# 03_LED.net
KiCad netlist of a schematic drawn in Altium Designer
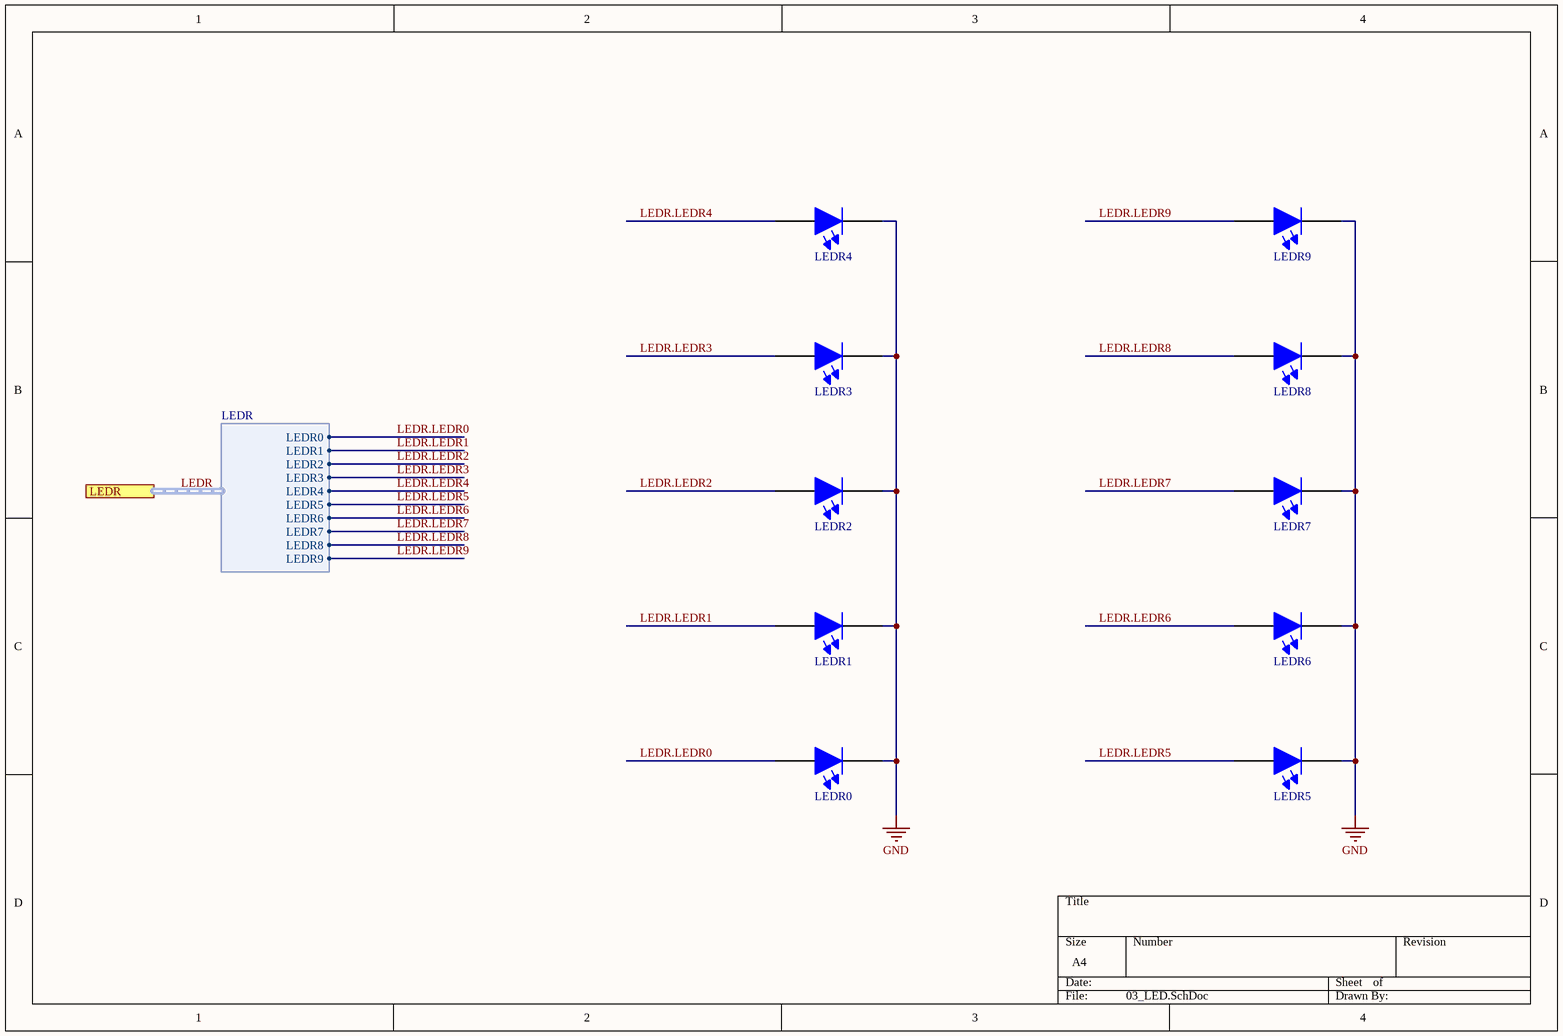
[diagram p0: 03_LED.SchDoc]

(export (version "E")
  (design (tool "Eeschema 10.0.6"))
  (components
    (comp (ref "LEDR0")
      (value "LED")
      (footprint "0805D-RED")
      (description "Generic LED")
      (fields
        (field (name "01 CREATED BY") "Thomas Harper")
        (field (name "02 REVIEWED BY") "Rodrigo Maureira @ 2018-04-05")
        (field (name "PUBLISHER") "MUEEC")
      )
      (libsource (lib "Quatro_SchLib") (part "LED_SMD_Generic"))
    )
    (comp (ref "LEDR1")
      (value "LED")
      (footprint "0805D-RED")
      (description "Generic LED")
      (fields
        (field (name "01 CREATED BY") "Thomas Harper")
        (field (name "02 REVIEWED BY") "Rodrigo Maureira @ 2018-04-05")
        (field (name "PUBLISHER") "MUEEC")
      )
      (libsource (lib "Quatro_SchLib") (part "LED_SMD_Generic"))
    )
    (comp (ref "LEDR2")
      (value "LED")
      (footprint "0805D-RED")
      (description "Generic LED")
      (fields
        (field (name "01 CREATED BY") "Thomas Harper")
        (field (name "02 REVIEWED BY") "Rodrigo Maureira @ 2018-04-05")
        (field (name "PUBLISHER") "MUEEC")
      )
      (libsource (lib "Quatro_SchLib") (part "LED_SMD_Generic"))
    )
    (comp (ref "LEDR3")
      (value "LED")
      (footprint "0805D-RED")
      (description "Generic LED")
      (fields
        (field (name "01 CREATED BY") "Thomas Harper")
        (field (name "02 REVIEWED BY") "Rodrigo Maureira @ 2018-04-05")
        (field (name "PUBLISHER") "MUEEC")
      )
      (libsource (lib "Quatro_SchLib") (part "LED_SMD_Generic"))
    )
    (comp (ref "LEDR4")
      (value "LED")
      (footprint "0805D-RED")
      (description "Generic LED")
      (fields
        (field (name "01 CREATED BY") "Thomas Harper")
        (field (name "02 REVIEWED BY") "Rodrigo Maureira @ 2018-04-05")
        (field (name "PUBLISHER") "MUEEC")
      )
      (libsource (lib "Quatro_SchLib") (part "LED_SMD_Generic"))
    )
    (comp (ref "LEDR5")
      (value "LED")
      (footprint "0805D-RED")
      (description "Generic LED")
      (fields
        (field (name "01 CREATED BY") "Thomas Harper")
        (field (name "02 REVIEWED BY") "Rodrigo Maureira @ 2018-04-05")
        (field (name "PUBLISHER") "MUEEC")
      )
      (libsource (lib "Quatro_SchLib") (part "LED_SMD_Generic"))
    )
    (comp (ref "LEDR6")
      (value "LED")
      (footprint "0805D-RED")
      (description "Generic LED")
      (fields
        (field (name "01 CREATED BY") "Thomas Harper")
        (field (name "02 REVIEWED BY") "Rodrigo Maureira @ 2018-04-05")
        (field (name "PUBLISHER") "MUEEC")
      )
      (libsource (lib "Quatro_SchLib") (part "LED_SMD_Generic"))
    )
    (comp (ref "LEDR7")
      (value "LED")
      (footprint "0805D-RED")
      (description "Generic LED")
      (fields
        (field (name "01 CREATED BY") "Thomas Harper")
        (field (name "02 REVIEWED BY") "Rodrigo Maureira @ 2018-04-05")
        (field (name "PUBLISHER") "MUEEC")
      )
      (libsource (lib "Quatro_SchLib") (part "LED_SMD_Generic"))
    )
    (comp (ref "LEDR8")
      (value "LED")
      (footprint "0805D-RED")
      (description "Generic LED")
      (fields
        (field (name "01 CREATED BY") "Thomas Harper")
        (field (name "02 REVIEWED BY") "Rodrigo Maureira @ 2018-04-05")
        (field (name "PUBLISHER") "MUEEC")
      )
      (libsource (lib "Quatro_SchLib") (part "LED_SMD_Generic"))
    )
    (comp (ref "LEDR9")
      (value "LED")
      (footprint "0805D-RED")
      (description "Generic LED")
      (fields
        (field (name "01 CREATED BY") "Thomas Harper")
        (field (name "02 REVIEWED BY") "Rodrigo Maureira @ 2018-04-05")
        (field (name "PUBLISHER") "MUEEC")
      )
      (libsource (lib "Quatro_SchLib") (part "LED_SMD_Generic"))
    )
  )
  (nets
    (net (code "2") (name "/LEDR.LEDR0") (class "Default")
      (node (ref "LEDR0") (pin "A") (pinfunction "ANODE_A") (pintype "passive"))
    )
    (net (code "3") (name "/LEDR.LEDR1") (class "Default")
      (node (ref "LEDR1") (pin "A") (pinfunction "ANODE_A") (pintype "passive"))
    )
    (net (code "4") (name "/LEDR.LEDR2") (class "Default")
      (node (ref "LEDR2") (pin "A") (pinfunction "ANODE_A") (pintype "passive"))
    )
    (net (code "5") (name "/LEDR.LEDR3") (class "Default")
      (node (ref "LEDR3") (pin "A") (pinfunction "ANODE_A") (pintype "passive"))
    )
    (net (code "6") (name "/LEDR.LEDR4") (class "Default")
      (node (ref "LEDR4") (pin "A") (pinfunction "ANODE_A") (pintype "passive"))
    )
    (net (code "7") (name "/LEDR.LEDR5") (class "Default")
      (node (ref "LEDR5") (pin "A") (pinfunction "ANODE_A") (pintype "passive"))
    )
    (net (code "8") (name "/LEDR.LEDR6") (class "Default")
      (node (ref "LEDR6") (pin "A") (pinfunction "ANODE_A") (pintype "passive"))
    )
    (net (code "9") (name "/LEDR.LEDR7") (class "Default")
      (node (ref "LEDR7") (pin "A") (pinfunction "ANODE_A") (pintype "passive"))
    )
    (net (code "10") (name "/LEDR.LEDR8") (class "Default")
      (node (ref "LEDR8") (pin "A") (pinfunction "ANODE_A") (pintype "passive"))
    )
    (net (code "11") (name "/LEDR.LEDR9") (class "Default")
      (node (ref "LEDR9") (pin "A") (pinfunction "ANODE_A") (pintype "passive"))
    )
    (net (code "13") (name "GND") (class "Default")
      (node (ref "LEDR0") (pin "K") (pinfunction "CATHODE_K") (pintype "passive"))
      (node (ref "LEDR1") (pin "K") (pinfunction "CATHODE_K") (pintype "passive"))
      (node (ref "LEDR2") (pin "K") (pinfunction "CATHODE_K") (pintype "passive"))
      (node (ref "LEDR3") (pin "K") (pinfunction "CATHODE_K") (pintype "passive"))
      (node (ref "LEDR4") (pin "K") (pinfunction "CATHODE_K") (pintype "passive"))
      (node (ref "LEDR5") (pin "K") (pinfunction "CATHODE_K") (pintype "passive"))
      (node (ref "LEDR6") (pin "K") (pinfunction "CATHODE_K") (pintype "passive"))
      (node (ref "LEDR7") (pin "K") (pinfunction "CATHODE_K") (pintype "passive"))
      (node (ref "LEDR8") (pin "K") (pinfunction "CATHODE_K") (pintype "passive"))
      (node (ref "LEDR9") (pin "K") (pinfunction "CATHODE_K") (pintype "passive"))
    )
  )
)
